# Keg_Cop_-_Pinout.net
KiCad netlist of a schematic drawn in EAGLE
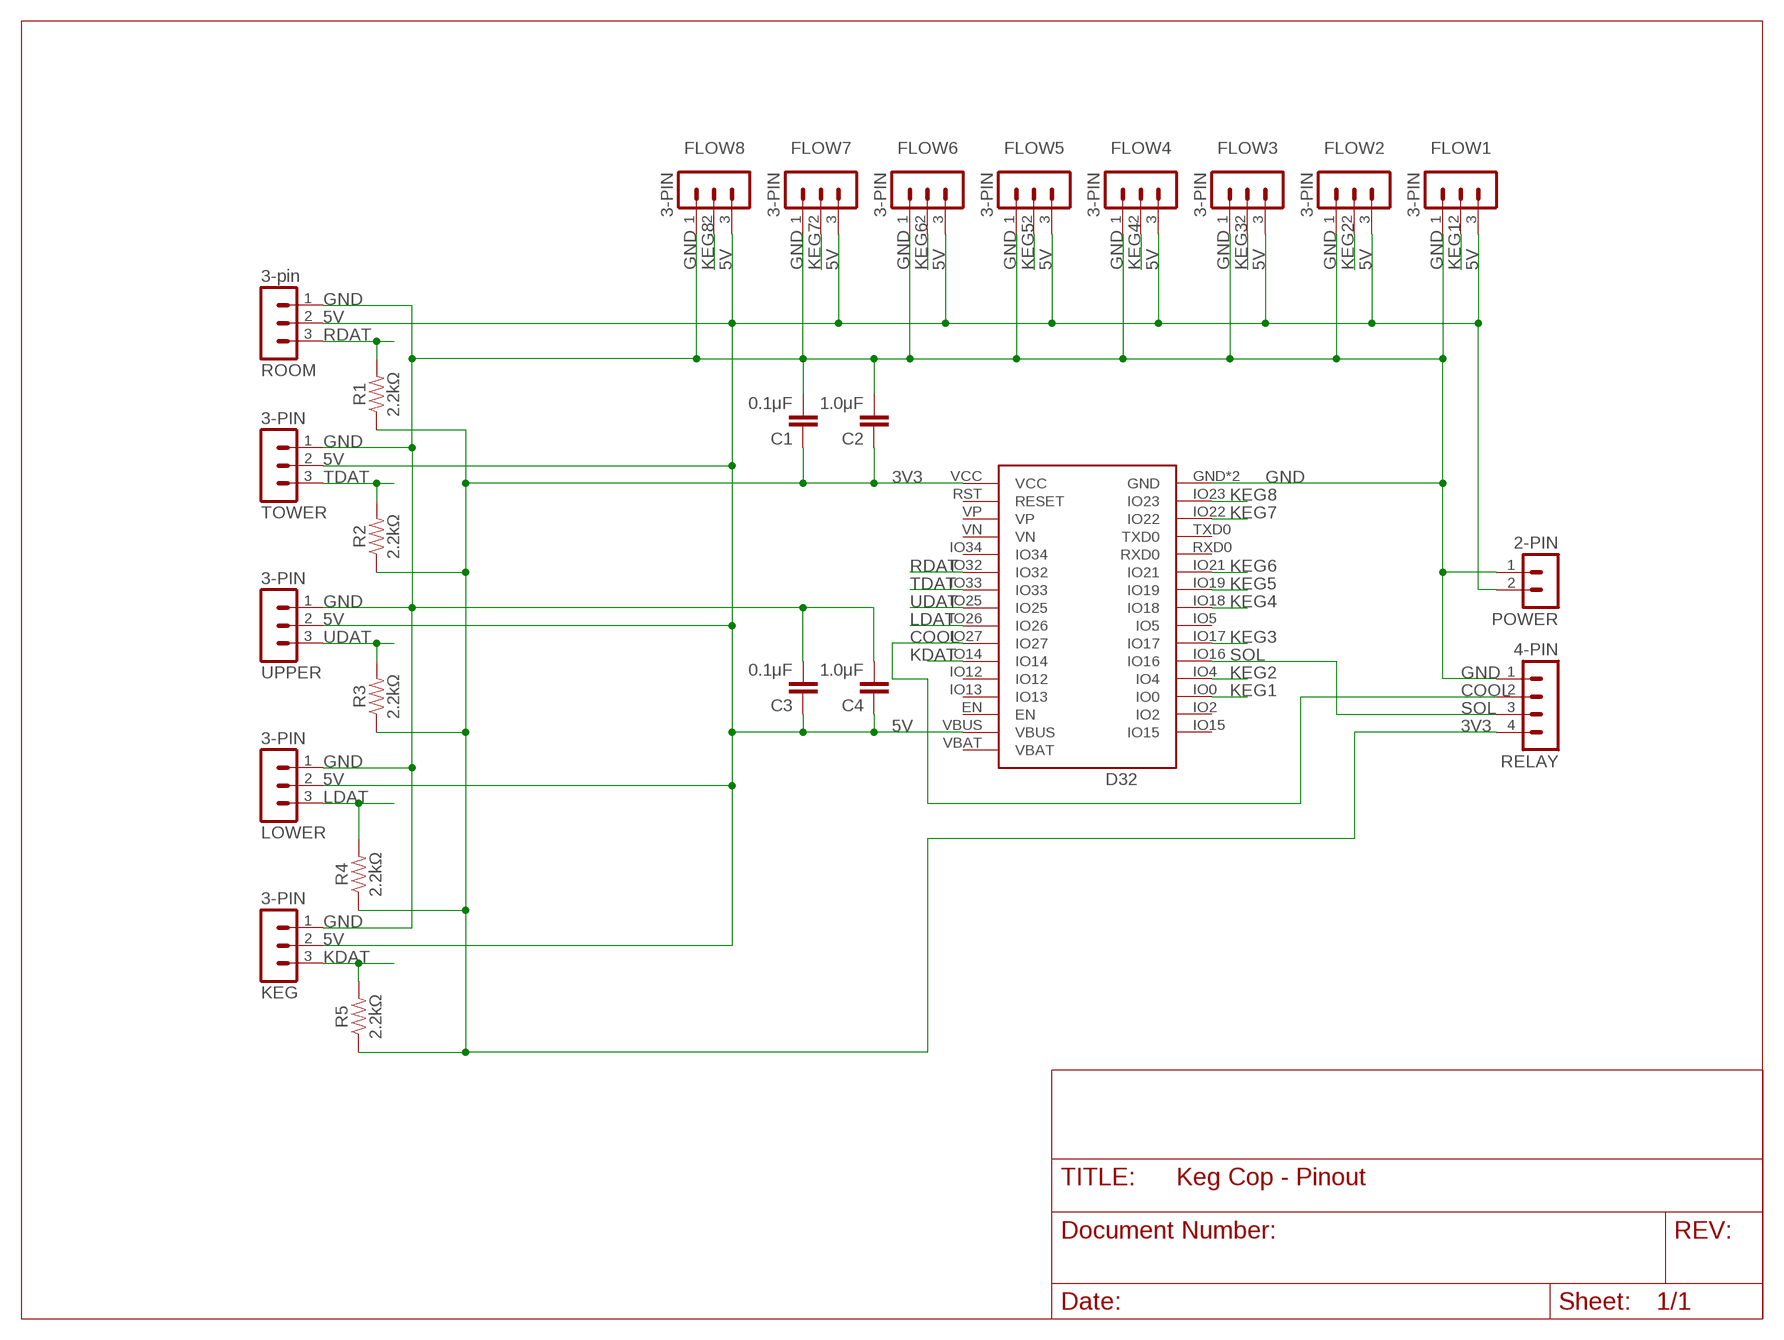
[diagram p0: schematic, sheet 1]

(export (version "E")
  (design (tool "Eeschema 10.0.6"))
  (components
    (comp (ref "C1")
      (value "0.1μF")
      (footprint "eagle-import:CAP_PTH-2.54")
      (libsource (lib "eagle-import") (part "CAP_CERAMIC_2.54"))
    )
    (comp (ref "C2")
      (value "1.0μF")
      (footprint "eagle-import:CAP_PTH-2.54")
      (libsource (lib "eagle-import") (part "CAP_CERAMIC_2.54"))
    )
    (comp (ref "C3")
      (value "0.1μF")
      (footprint "eagle-import:CAP_PTH-2.54")
      (libsource (lib "eagle-import") (part "CAP_CERAMIC_2.54"))
    )
    (comp (ref "C4")
      (value "1.0μF")
      (footprint "eagle-import:CAP_PTH-2.54")
      (libsource (lib "eagle-import") (part "CAP_CERAMIC_2.54"))
    )
    (comp (ref "D32")
      (value "U1")
      (footprint "eagle-import:D32_NO_BATT")
      (libsource (lib "eagle-import") (part "WEMOS-D32D32_NO_BATT"))
    )
    (comp (ref "FLOW1")
      (value "3-PIN")
      (footprint "eagle-import:MA03-1")
      (libsource (lib "eagle-import") (part "MA03-1"))
    )
    (comp (ref "FLOW2")
      (value "3-PIN")
      (footprint "eagle-import:MA03-1")
      (libsource (lib "eagle-import") (part "MA03-1"))
    )
    (comp (ref "FLOW3")
      (value "3-PIN")
      (footprint "eagle-import:MA03-1")
      (libsource (lib "eagle-import") (part "MA03-1"))
    )
    (comp (ref "FLOW4")
      (value "3-PIN")
      (footprint "eagle-import:MA03-1")
      (libsource (lib "eagle-import") (part "MA03-1"))
    )
    (comp (ref "FLOW5")
      (value "3-PIN")
      (footprint "eagle-import:MA03-1")
      (libsource (lib "eagle-import") (part "MA03-1"))
    )
    (comp (ref "FLOW6")
      (value "3-PIN")
      (footprint "eagle-import:MA03-1")
      (libsource (lib "eagle-import") (part "MA03-1"))
    )
    (comp (ref "FLOW7")
      (value "3-PIN")
      (footprint "eagle-import:MA03-1")
      (libsource (lib "eagle-import") (part "MA03-1"))
    )
    (comp (ref "FLOW8")
      (value "3-PIN")
      (footprint "eagle-import:MA03-1")
      (libsource (lib "eagle-import") (part "MA03-1"))
    )
    (comp (ref "KEG")
      (value "3-PIN")
      (footprint "eagle-import:MA03-1")
      (libsource (lib "eagle-import") (part "MA03-1"))
    )
    (comp (ref "LOWER")
      (value "3-PIN")
      (footprint "eagle-import:MA03-1")
      (libsource (lib "eagle-import") (part "MA03-1"))
    )
    (comp (ref "POWER")
      (value "2-PIN")
      (footprint "eagle-import:HDR-2_VERT")
      (libsource (lib "eagle-import") (part "HDR-2"))
    )
    (comp (ref "R1")
      (value "2.2kΩ")
      (footprint "eagle-import:AXIAL-0.3")
      (libsource (lib "eagle-import") (part "RESISTORAXIAL-0.3"))
    )
    (comp (ref "R2")
      (value "2.2kΩ")
      (footprint "eagle-import:AXIAL-0.3")
      (libsource (lib "eagle-import") (part "RESISTORAXIAL-0.3"))
    )
    (comp (ref "R3")
      (value "2.2kΩ")
      (footprint "eagle-import:AXIAL-0.3")
      (libsource (lib "eagle-import") (part "RESISTORAXIAL-0.3"))
    )
    (comp (ref "R4")
      (value "2.2kΩ")
      (footprint "eagle-import:AXIAL-0.3")
      (libsource (lib "eagle-import") (part "RESISTORAXIAL-0.3"))
    )
    (comp (ref "R5")
      (value "2.2kΩ")
      (footprint "eagle-import:AXIAL-0.3")
      (libsource (lib "eagle-import") (part "RESISTORAXIAL-0.3"))
    )
    (comp (ref "RELAY")
      (value "4-PIN")
      (footprint "eagle-import:MA04-1")
      (libsource (lib "eagle-import") (part "MA04-1"))
    )
    (comp (ref "ROOM")
      (value "3-pin")
      (footprint "eagle-import:MA03-1")
      (libsource (lib "eagle-import") (part "MA03-1"))
    )
    (comp (ref "TOWER")
      (value "3-PIN")
      (footprint "eagle-import:MA03-1")
      (libsource (lib "eagle-import") (part "MA03-1"))
    )
    (comp (ref "UPPER")
      (value "3-PIN")
      (footprint "eagle-import:MA03-1")
      (libsource (lib "eagle-import") (part "MA03-1"))
    )
  )
  (nets
    (net (code "1") (name "/3V3") (class "Default")
      (node (ref "C1") (pin "1") (pinfunction "1_1") (pintype "passive"))
      (node (ref "C2") (pin "1") (pinfunction "1_1") (pintype "passive"))
      (node (ref "D32") (pin "VCC") (pinfunction "VCC_VCC") (pintype "power_in"))
      (node (ref "R1") (pin "P$1") (pinfunction "1_P$1") (pintype "passive"))
      (node (ref "R2") (pin "P$1") (pinfunction "1_P$1") (pintype "passive"))
      (node (ref "R3") (pin "P$1") (pinfunction "1_P$1") (pintype "passive"))
      (node (ref "R4") (pin "P$1") (pinfunction "1_P$1") (pintype "passive"))
      (node (ref "R5") (pin "P$1") (pinfunction "1_P$1") (pintype "passive"))
      (node (ref "RELAY") (pin "4") (pinfunction "4_4") (pintype "passive"))
    )
    (net (code "2") (name "/5V") (class "Default")
      (node (ref "C3") (pin "1") (pinfunction "1_1") (pintype "passive"))
      (node (ref "C4") (pin "1") (pinfunction "1_1") (pintype "passive"))
      (node (ref "D32") (pin "VBUS") (pinfunction "VBUS_VBUS") (pintype "bidirectional"))
      (node (ref "FLOW1") (pin "3") (pinfunction "3_3") (pintype "passive"))
      (node (ref "FLOW2") (pin "3") (pinfunction "3_3") (pintype "passive"))
      (node (ref "FLOW3") (pin "3") (pinfunction "3_3") (pintype "passive"))
      (node (ref "FLOW4") (pin "3") (pinfunction "3_3") (pintype "passive"))
      (node (ref "FLOW5") (pin "3") (pinfunction "3_3") (pintype "passive"))
      (node (ref "FLOW6") (pin "3") (pinfunction "3_3") (pintype "passive"))
      (node (ref "FLOW7") (pin "3") (pinfunction "3_3") (pintype "passive"))
      (node (ref "FLOW8") (pin "3") (pinfunction "3_3") (pintype "passive"))
      (node (ref "KEG") (pin "2") (pinfunction "2_2") (pintype "passive"))
      (node (ref "LOWER") (pin "2") (pinfunction "2_2") (pintype "passive"))
      (node (ref "POWER") (pin "2") (pinfunction "2_2") (pintype "passive"))
      (node (ref "ROOM") (pin "2") (pinfunction "2_2") (pintype "passive"))
      (node (ref "TOWER") (pin "2") (pinfunction "2_2") (pintype "passive"))
      (node (ref "UPPER") (pin "2") (pinfunction "2_2") (pintype "passive"))
    )
    (net (code "3") (name "/COOL") (class "Default")
      (node (ref "D32") (pin "IO27") (pinfunction "IO27_IO27") (pintype "bidirectional"))
      (node (ref "RELAY") (pin "2") (pinfunction "2_2") (pintype "passive"))
    )
    (net (code "4") (name "/GND") (class "Default")
      (node (ref "C1") (pin "2") (pinfunction "2_2") (pintype "passive"))
      (node (ref "C2") (pin "2") (pinfunction "2_2") (pintype "passive"))
      (node (ref "C3") (pin "2") (pinfunction "2_2") (pintype "passive"))
      (node (ref "C4") (pin "2") (pinfunction "2_2") (pintype "passive"))
      (node (ref "D32") (pin "GND") (pinfunction "GND_GND") (pintype "power_in"))
      (node (ref "D32") (pin "GND2") (pinfunction "GND_GND2") (pintype "power_in"))
      (node (ref "FLOW1") (pin "1") (pinfunction "1_1") (pintype "passive"))
      (node (ref "FLOW2") (pin "1") (pinfunction "1_1") (pintype "passive"))
      (node (ref "FLOW3") (pin "1") (pinfunction "1_1") (pintype "passive"))
      (node (ref "FLOW4") (pin "1") (pinfunction "1_1") (pintype "passive"))
      (node (ref "FLOW5") (pin "1") (pinfunction "1_1") (pintype "passive"))
      (node (ref "FLOW6") (pin "1") (pinfunction "1_1") (pintype "passive"))
      (node (ref "FLOW7") (pin "1") (pinfunction "1_1") (pintype "passive"))
      (node (ref "FLOW8") (pin "1") (pinfunction "1_1") (pintype "passive"))
      (node (ref "KEG") (pin "1") (pinfunction "1_1") (pintype "passive"))
      (node (ref "LOWER") (pin "1") (pinfunction "1_1") (pintype "passive"))
      (node (ref "POWER") (pin "1") (pinfunction "1_1") (pintype "passive"))
      (node (ref "RELAY") (pin "1") (pinfunction "1_1") (pintype "passive"))
      (node (ref "ROOM") (pin "1") (pinfunction "1_1") (pintype "passive"))
      (node (ref "TOWER") (pin "1") (pinfunction "1_1") (pintype "passive"))
      (node (ref "UPPER") (pin "1") (pinfunction "1_1") (pintype "passive"))
    )
    (net (code "5") (name "/KDAT") (class "Default")
      (node (ref "D32") (pin "IO14") (pinfunction "IO14_IO14") (pintype "bidirectional"))
      (node (ref "KEG") (pin "3") (pinfunction "3_3") (pintype "passive"))
      (node (ref "R5") (pin "P$2") (pinfunction "2_P$2") (pintype "passive"))
    )
    (net (code "6") (name "/KEG1") (class "Default")
      (node (ref "D32") (pin "IO0") (pinfunction "IO0_IO0") (pintype "bidirectional"))
      (node (ref "FLOW1") (pin "2") (pinfunction "2_2") (pintype "passive"))
    )
    (net (code "7") (name "/KEG2") (class "Default")
      (node (ref "D32") (pin "IO4") (pinfunction "IO4_IO4") (pintype "bidirectional"))
      (node (ref "FLOW2") (pin "2") (pinfunction "2_2") (pintype "passive"))
    )
    (net (code "8") (name "/KEG3") (class "Default")
      (node (ref "D32") (pin "IO17") (pinfunction "IO17_IO17") (pintype "bidirectional"))
      (node (ref "FLOW3") (pin "2") (pinfunction "2_2") (pintype "passive"))
    )
    (net (code "9") (name "/KEG4") (class "Default")
      (node (ref "D32") (pin "IO18") (pinfunction "IO18_IO18") (pintype "bidirectional"))
      (node (ref "FLOW4") (pin "2") (pinfunction "2_2") (pintype "passive"))
    )
    (net (code "10") (name "/KEG5") (class "Default")
      (node (ref "D32") (pin "IO19") (pinfunction "IO19_IO19") (pintype "bidirectional"))
      (node (ref "FLOW5") (pin "2") (pinfunction "2_2") (pintype "passive"))
    )
    (net (code "11") (name "/KEG6") (class "Default")
      (node (ref "D32") (pin "IO21") (pinfunction "IO21_IO21") (pintype "bidirectional"))
      (node (ref "FLOW6") (pin "2") (pinfunction "2_2") (pintype "passive"))
    )
    (net (code "12") (name "/KEG7") (class "Default")
      (node (ref "D32") (pin "IO22") (pinfunction "IO22_IO22") (pintype "bidirectional"))
      (node (ref "FLOW7") (pin "2") (pinfunction "2_2") (pintype "passive"))
    )
    (net (code "13") (name "/KEG8") (class "Default")
      (node (ref "D32") (pin "IO23") (pinfunction "IO23_IO23") (pintype "bidirectional"))
      (node (ref "FLOW8") (pin "2") (pinfunction "2_2") (pintype "passive"))
    )
    (net (code "14") (name "/LDAT") (class "Default")
      (node (ref "D32") (pin "IO26") (pinfunction "IO26_IO26") (pintype "bidirectional"))
      (node (ref "LOWER") (pin "3") (pinfunction "3_3") (pintype "passive"))
      (node (ref "R4") (pin "P$2") (pinfunction "2_P$2") (pintype "passive"))
    )
    (net (code "15") (name "/RDAT") (class "Default")
      (node (ref "D32") (pin "IO32") (pinfunction "IO32_IO32") (pintype "bidirectional"))
      (node (ref "R1") (pin "P$2") (pinfunction "2_P$2") (pintype "passive"))
      (node (ref "ROOM") (pin "3") (pinfunction "3_3") (pintype "passive"))
    )
    (net (code "16") (name "/SOL") (class "Default")
      (node (ref "D32") (pin "IO16") (pinfunction "IO16_IO16") (pintype "bidirectional"))
      (node (ref "RELAY") (pin "3") (pinfunction "3_3") (pintype "passive"))
    )
    (net (code "17") (name "/TDAT") (class "Default")
      (node (ref "D32") (pin "IO33") (pinfunction "IO33_IO33") (pintype "bidirectional"))
      (node (ref "R2") (pin "P$2") (pinfunction "2_P$2") (pintype "passive"))
      (node (ref "TOWER") (pin "3") (pinfunction "3_3") (pintype "passive"))
    )
    (net (code "18") (name "/UDAT") (class "Default")
      (node (ref "D32") (pin "IO25") (pinfunction "IO25_IO25") (pintype "bidirectional"))
      (node (ref "R3") (pin "P$2") (pinfunction "2_P$2") (pintype "passive"))
      (node (ref "UPPER") (pin "3") (pinfunction "3_3") (pintype "passive"))
    )
    (net (code "19") (name "unconnected-(D32-PadEN)") (class "Default")
      (node (ref "D32") (pin "EN") (pinfunction "EN_EN") (pintype "bidirectional"))
    )
    (net (code "20") (name "unconnected-(D32-PadIO2)") (class "Default")
      (node (ref "D32") (pin "IO2") (pinfunction "IO2_IO2") (pintype "bidirectional"))
    )
    (net (code "21") (name "unconnected-(D32-PadIO5)") (class "Default")
      (node (ref "D32") (pin "IO5") (pinfunction "IO5_IO5") (pintype "bidirectional"))
    )
    (net (code "22") (name "unconnected-(D32-PadIO12)") (class "Default")
      (node (ref "D32") (pin "IO12") (pinfunction "IO12_IO12") (pintype "bidirectional"))
    )
    (net (code "23") (name "unconnected-(D32-PadIO13)") (class "Default")
      (node (ref "D32") (pin "IO13") (pinfunction "IO13_IO13") (pintype "bidirectional"))
    )
    (net (code "24") (name "unconnected-(D32-PadIO15)") (class "Default")
      (node (ref "D32") (pin "IO15") (pinfunction "IO15_IO15") (pintype "bidirectional"))
    )
    (net (code "25") (name "unconnected-(D32-PadIO34)") (class "Default")
      (node (ref "D32") (pin "IO34") (pinfunction "IO34_IO34") (pintype "bidirectional"))
    )
    (net (code "26") (name "unconnected-(D32-PadRXD0)") (class "Default")
      (node (ref "D32") (pin "RXD0") (pinfunction "RXD0_RXD0") (pintype "input"))
    )
    (net (code "27") (name "unconnected-(D32-PadTXD0)") (class "Default")
      (node (ref "D32") (pin "TXD0") (pinfunction "TXD0_TXD0") (pintype "output"))
    )
    (net (code "28") (name "unconnected-(D32-PadVBAT)") (class "Default")
      (node (ref "D32") (pin "VBAT") (pinfunction "VBAT_VBAT") (pintype "bidirectional"))
    )
    (net (code "29") (name "unconnected-(D32-PadVN)") (class "Default")
      (node (ref "D32") (pin "VN") (pinfunction "VN_VN") (pintype "bidirectional"))
    )
    (net (code "30") (name "unconnected-(D32-PadVP)") (class "Default")
      (node (ref "D32") (pin "VP") (pinfunction "VP_VP") (pintype "bidirectional"))
    )
    (net (code "31") (name "unconnected-(D32-RESET-PadRST)") (class "Default")
      (node (ref "D32") (pin "RST") (pinfunction "RESET_RST") (pintype "bidirectional"))
    )
  )
)
